# biochem_M_V2.net
KiCad netlist of a schematic drawn in EAGLE
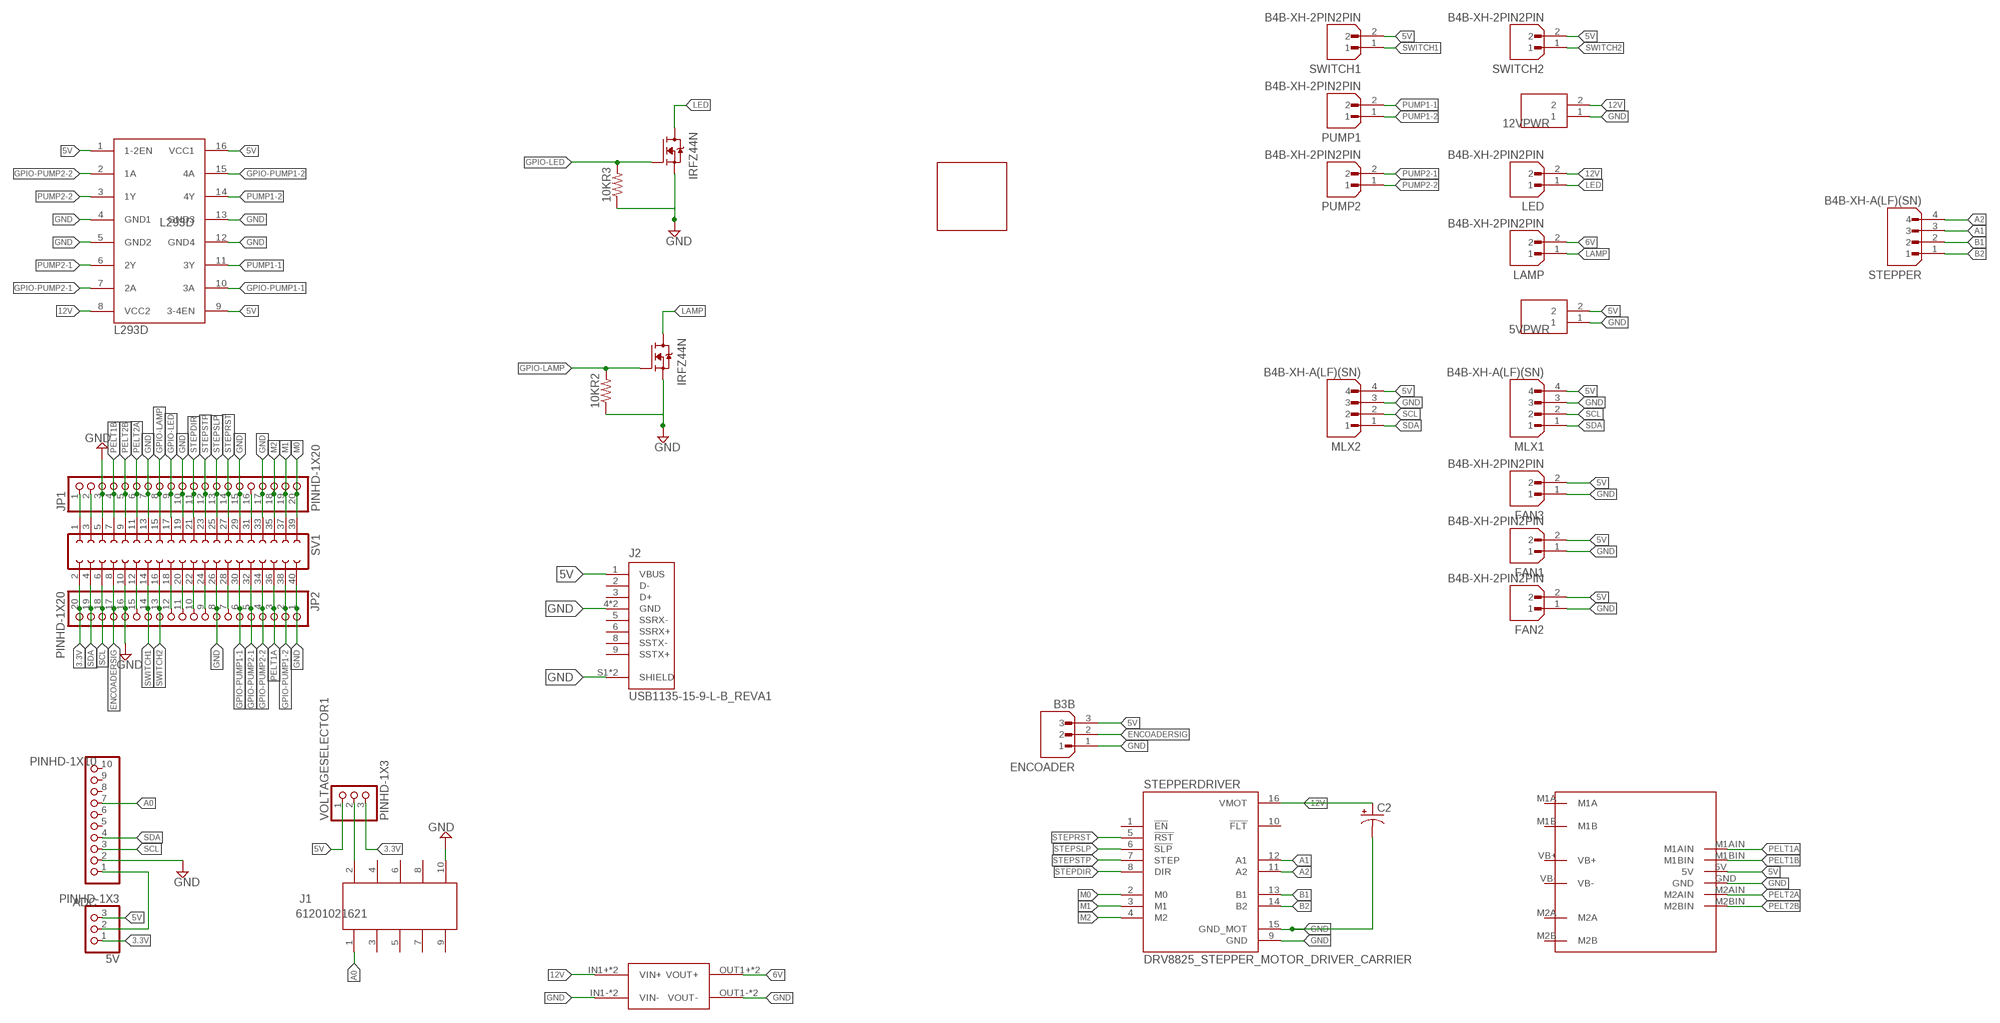
[diagram p0: schematic, sheet 1]

(export (version "E")
  (design (tool "Eeschema 10.0.6"))
  (components
    (comp (ref "5V")
      (value "PINHD-1X3")
      (footprint "eagle-import:1X03")
      (libsource (lib "eagle-import") (part "PINHD-1X3"))
    )
    (comp (ref "5VPWR")
      (value "TB010-508-02BE")
      (footprint "eagle-import:CUI_TB010-508-02BE")
      (fields (field (name "MF") "CUI Devices"))
      (libsource (lib "eagle-import") (part "TB010-508-02BE"))
    )
    (comp (ref "10KR2")
      (value "R-US_0204/7")
      (footprint "eagle-import:0204_7")
      (libsource (lib "eagle-import") (part "R-US_0204/7"))
    )
    (comp (ref "10KR3")
      (value "R-US_0204/7")
      (footprint "eagle-import:0204_7")
      (libsource (lib "eagle-import") (part "R-US_0204/7"))
    )
    (comp (ref "12VPWR")
      (value "TB010-508-02BE")
      (footprint "eagle-import:CUI_TB010-508-02BE")
      (fields (field (name "MF") "CUI Devices"))
      (libsource (lib "eagle-import") (part "TB010-508-02BE"))
    )
    (comp (ref "ADC")
      (value "PINHD-1X10")
      (footprint "eagle-import:1X10")
      (libsource (lib "eagle-import") (part "PINHD-1X10"))
    )
    (comp (ref "C2")
      (value "CPOL-USB45181A")
      (footprint "eagle-import:B45181A")
      (libsource (lib "eagle-import") (part "CPOL-USB45181A"))
    )
    (comp (ref "ENCOADER")
      (value "B3B")
      (footprint "eagle-import:B3B")
      (libsource (lib "eagle-import") (part "B3B"))
    )
    (comp (ref "FAN1")
      (value "B4B-XH-2PIN2PIN")
      (footprint "eagle-import:B4BXH2")
      (libsource (lib "eagle-import") (part "B4B-XH-2PIN2PIN"))
    )
    (comp (ref "FAN2")
      (value "B4B-XH-2PIN2PIN")
      (footprint "eagle-import:B4BXH2")
      (libsource (lib "eagle-import") (part "B4B-XH-2PIN2PIN"))
    )
    (comp (ref "FAN3")
      (value "B4B-XH-2PIN2PIN")
      (footprint "eagle-import:B4BXH2")
      (libsource (lib "eagle-import") (part "B4B-XH-2PIN2PIN"))
    )
    (comp (ref "J1")
      (value "61201021621")
      (footprint "eagle-import:61201021621")
      (fields (field (name "MF") "Wurth Elektronik"))
      (libsource (lib "eagle-import") (part "61201021621"))
    )
    (comp (ref "J2")
      (value "USB1135-15-9-L-B_REVA1")
      (footprint "eagle-import:GCT_USB1135-15-9-L-B_REVA1")
      (fields (field (name "MF") "Global Connector Technology") (field (name "MP") "USB1135-15-9-L-B"))
      (libsource (lib "eagle-import") (part "USB1135-15-9-L-B_REVA1"))
    )
    (comp (ref "JP1")
      (value "PINHD-1X20")
      (footprint "eagle-import:1X20")
      (libsource (lib "eagle-import") (part "PINHD-1X20"))
    )
    (comp (ref "JP2")
      (value "PINHD-1X20")
      (footprint "eagle-import:1X20")
      (libsource (lib "eagle-import") (part "PINHD-1X20"))
    )
    (comp (ref "L293D")
      (value "L293D")
      (footprint "eagle-import:DIL16")
      (libsource (lib "eagle-import") (part "L293D"))
    )
    (comp (ref "LAMP")
      (value "B4B-XH-2PIN2PIN")
      (footprint "eagle-import:B4BXH2")
      (libsource (lib "eagle-import") (part "B4B-XH-2PIN2PIN"))
    )
    (comp (ref "LED")
      (value "B4B-XH-2PIN2PIN")
      (footprint "eagle-import:B4BXH2")
      (libsource (lib "eagle-import") (part "B4B-XH-2PIN2PIN"))
    )
    (comp (ref "MLX1")
      (value "B4B-XH-A(LF)(SN)")
      (footprint "eagle-import:JST_B4B-XH-A(LF)(SN)")
      (fields (field (name "MF") "JST") (field (name "MP") "B4B-XH-A  (LF)(SN)"))
      (libsource (lib "eagle-import") (part "B4B-XH-A(LF)(SN)"))
    )
    (comp (ref "MLX2")
      (value "B4B-XH-A(LF)(SN)")
      (footprint "eagle-import:JST_B4B-XH-A(LF)(SN)")
      (fields (field (name "MF") "JST") (field (name "MP") "B4B-XH-A  (LF)(SN)"))
      (libsource (lib "eagle-import") (part "B4B-XH-A(LF)(SN)"))
    )
    (comp (ref "PUMP1")
      (value "B4B-XH-2PIN2PIN")
      (footprint "eagle-import:B4BXH2")
      (libsource (lib "eagle-import") (part "B4B-XH-2PIN2PIN"))
    )
    (comp (ref "PUMP2")
      (value "B4B-XH-2PIN2PIN")
      (footprint "eagle-import:B4BXH2")
      (libsource (lib "eagle-import") (part "B4B-XH-2PIN2PIN"))
    )
    (comp (ref "Q4-T")
      (value "IRFZ44N")
      (footprint "eagle-import:TO254P1016X419X2286-3")
      (fields (field (name "MF") "Infineon Technologies"))
      (libsource (lib "eagle-import") (part "IRFZ44N"))
    )
    (comp (ref "Q4-T4")
      (value "IRFZ44N")
      (footprint "eagle-import:TO254P1016X419X2286-3")
      (fields (field (name "MF") "Infineon Technologies"))
      (libsource (lib "eagle-import") (part "IRFZ44N"))
    )
    (comp (ref "STEPPER")
      (value "B4B-XH-A(LF)(SN)")
      (footprint "eagle-import:JST_B4B-XH-A(LF)(SN)")
      (fields (field (name "MF") "JST") (field (name "MP") "B4B-XH-A  (LF)(SN)"))
      (libsource (lib "eagle-import") (part "B4B-XH-A(LF)(SN)"))
    )
    (comp (ref "STEPPERDRIVER")
      (value "DRV8825_STEPPER_MOTOR_DRIVER_CARRIER")
      (footprint "eagle-import:IC_DRV8825_STEPPER_MOTOR_DRIVER_CARRIER")
      (fields (field (name "MF") "Pololu") (field (name "MP") "DRV8825 STEPPER MOTOR DRIVER CARRIER"))
      (libsource (lib "eagle-import") (part "DRV8825_STEPPER_MOTOR_DRIVER_CARRIER"))
    )
    (comp (ref "SV1")
      (value "FE20-2")
      (footprint "eagle-import:FE20-2")
      (libsource (lib "eagle-import") (part "FE20-2"))
    )
    (comp (ref "SWITCH1")
      (value "B4B-XH-2PIN2PIN")
      (footprint "eagle-import:B4BXH2")
      (libsource (lib "eagle-import") (part "B4B-XH-2PIN2PIN"))
    )
    (comp (ref "SWITCH2")
      (value "B4B-XH-2PIN2PIN")
      (footprint "eagle-import:B4BXH2")
      (libsource (lib "eagle-import") (part "B4B-XH-2PIN2PIN"))
    )
    (comp (ref "U$1")
      (value "MP1584")
      (footprint "eagle-import:DC-BRICK")
      (libsource (lib "eagle-import") (part "MP1584"))
    )
    (comp (ref "U$2")
      (value "MDD3A")
      (footprint "eagle-import:FOOTPRINT")
      (libsource (lib "eagle-import") (part "MDD3A"))
    )
    (comp (ref "U$3")
      (value "QRBIOS")
      (footprint "eagle-import:GITQRBIOSPECTRONICS")
      (libsource (lib "eagle-import") (part "QRBIOS"))
    )
    (comp (ref "VOLTAGESELECTOR1")
      (value "PINHD-1X3")
      (footprint "eagle-import:1X03")
      (libsource (lib "eagle-import") (part "PINHD-1X3"))
    )
  )
  (nets
    (net (code "1") (name "3.3V") (class "Default")
      (node (ref "5V") (pin "1") (pinfunction "1_1") (pintype "passive"))
      (node (ref "JP2") (pin "20") (pinfunction "20_20") (pintype "passive"))
      (node (ref "SV1") (pin "2") (pinfunction "2_2") (pintype "passive"))
      (node (ref "VOLTAGESELECTOR1") (pin "3") (pinfunction "3_3") (pintype "passive"))
    )
    (net (code "2") (name "5V") (class "Default")
      (node (ref "5V") (pin "3") (pinfunction "3_3") (pintype "passive"))
      (node (ref "5VPWR") (pin "2") (pinfunction "2_2") (pintype "passive"))
      (node (ref "ENCOADER") (pin "3") (pinfunction "3_3") (pintype "passive"))
      (node (ref "FAN1") (pin "2") (pinfunction "2_2") (pintype "passive"))
      (node (ref "FAN2") (pin "2") (pinfunction "2_2") (pintype "passive"))
      (node (ref "FAN3") (pin "2") (pinfunction "2_2") (pintype "passive"))
      (node (ref "J2") (pin "1") (pinfunction "VBUS_1") (pintype "power_in"))
      (node (ref "L293D") (pin "1") (pinfunction "1-2EN_1") (pintype "input"))
      (node (ref "L293D") (pin "16") (pinfunction "VCC1_16") (pintype "power_in"))
      (node (ref "L293D") (pin "9") (pinfunction "3-4EN_9") (pintype "input"))
      (node (ref "MLX1") (pin "4") (pinfunction "4_4") (pintype "passive"))
      (node (ref "MLX2") (pin "4") (pinfunction "4_4") (pintype "passive"))
      (node (ref "SWITCH1") (pin "2") (pinfunction "2_2") (pintype "passive"))
      (node (ref "SWITCH2") (pin "2") (pinfunction "2_2") (pintype "passive"))
      (node (ref "U$2") (pin "5V") (pinfunction "5V_5V") (pintype "bidirectional"))
      (node (ref "VOLTAGESELECTOR1") (pin "1") (pinfunction "1_1") (pintype "passive"))
    )
    (net (code "3") (name "6V") (class "Default")
      (node (ref "LAMP") (pin "2") (pinfunction "2_2") (pintype "passive"))
      (node (ref "U$1") (pin "OUT1+") (pinfunction "VOUT+_OUT1+") (pintype "output"))
      (node (ref "U$1") (pin "OUT2+") (pinfunction "VOUT+_OUT2+") (pintype "output"))
    )
    (net (code "4") (name "12V") (class "Default")
      (node (ref "12VPWR") (pin "2") (pinfunction "2_2") (pintype "passive"))
      (node (ref "C2") (pin "+") (pinfunction "+_+") (pintype "passive"))
      (node (ref "L293D") (pin "8") (pinfunction "VCC2_8") (pintype "power_in"))
      (node (ref "LED") (pin "2") (pinfunction "2_2") (pintype "passive"))
      (node (ref "STEPPERDRIVER") (pin "16") (pinfunction "VMOT_16") (pintype "power_in"))
      (node (ref "U$1") (pin "IN1+") (pinfunction "VIN+_IN1+") (pintype "input"))
      (node (ref "U$1") (pin "IN2+") (pinfunction "VIN+_IN2+") (pintype "input"))
    )
    (net (code "5") (name "A0") (class "Default")
      (node (ref "ADC") (pin "7") (pinfunction "7_7") (pintype "passive"))
      (node (ref "J1") (pin "1") (pinfunction "1_1") (pintype "passive"))
    )
    (net (code "6") (name "A1") (class "Default")
      (node (ref "STEPPER") (pin "3") (pinfunction "3_3") (pintype "passive"))
      (node (ref "STEPPERDRIVER") (pin "12") (pinfunction "A1_12") (pintype "output"))
    )
    (net (code "7") (name "A2") (class "Default")
      (node (ref "STEPPER") (pin "4") (pinfunction "4_4") (pintype "passive"))
      (node (ref "STEPPERDRIVER") (pin "11") (pinfunction "A2_11") (pintype "output"))
    )
    (net (code "8") (name "B1") (class "Default")
      (node (ref "STEPPER") (pin "2") (pinfunction "2_2") (pintype "passive"))
      (node (ref "STEPPERDRIVER") (pin "13") (pinfunction "B1_13") (pintype "output"))
    )
    (net (code "9") (name "B2") (class "Default")
      (node (ref "STEPPER") (pin "1") (pinfunction "1_1") (pintype "passive"))
      (node (ref "STEPPERDRIVER") (pin "14") (pinfunction "B2_14") (pintype "output"))
    )
    (net (code "10") (name "ENCOADERSIG") (class "Default")
      (node (ref "ENCOADER") (pin "2") (pinfunction "2_2") (pintype "passive"))
      (node (ref "JP2") (pin "17") (pinfunction "17_17") (pintype "passive"))
      (node (ref "SV1") (pin "8") (pinfunction "8_8") (pintype "passive"))
    )
    (net (code "11") (name "GND") (class "Default")
      (node (ref "10KR2") (pin "1") (pinfunction "1_1") (pintype "passive"))
      (node (ref "10KR3") (pin "1") (pinfunction "1_1") (pintype "passive"))
      (node (ref "12VPWR") (pin "1") (pinfunction "1_1") (pintype "passive"))
      (node (ref "5VPWR") (pin "1") (pinfunction "1_1") (pintype "passive"))
      (node (ref "ADC") (pin "2") (pinfunction "2_2") (pintype "passive"))
      (node (ref "C2") (pin "-") (pinfunction "-_-") (pintype "passive"))
      (node (ref "ENCOADER") (pin "1") (pinfunction "1_1") (pintype "passive"))
      (node (ref "FAN1") (pin "1") (pinfunction "1_1") (pintype "passive"))
      (node (ref "FAN2") (pin "1") (pinfunction "1_1") (pintype "passive"))
      (node (ref "FAN3") (pin "1") (pinfunction "1_1") (pintype "passive"))
      (node (ref "J1") (pin "10") (pinfunction "10_10") (pintype "passive"))
      (node (ref "J2") (pin "4") (pinfunction "GND_4") (pintype "power_in"))
      (node (ref "J2") (pin "7") (pinfunction "GND_7") (pintype "power_in"))
      (node (ref "J2") (pin "S1") (pinfunction "SHIELD_S1") (pintype "passive"))
      (node (ref "J2") (pin "S2") (pinfunction "SHIELD_S2") (pintype "passive"))
      (node (ref "JP1") (pin "10") (pinfunction "10_10") (pintype "passive"))
      (node (ref "JP1") (pin "15") (pinfunction "15_15") (pintype "passive"))
      (node (ref "JP1") (pin "17") (pinfunction "17_17") (pintype "passive"))
      (node (ref "JP1") (pin "3") (pinfunction "3_3") (pintype "passive"))
      (node (ref "JP1") (pin "7") (pinfunction "7_7") (pintype "passive"))
      (node (ref "JP2") (pin "1") (pinfunction "1_1") (pintype "passive"))
      (node (ref "JP2") (pin "16") (pinfunction "16_16") (pintype "passive"))
      (node (ref "JP2") (pin "8") (pinfunction "8_8") (pintype "passive"))
      (node (ref "L293D") (pin "12") (pinfunction "GND4_12") (pintype "power_in"))
      (node (ref "L293D") (pin "13") (pinfunction "GND3_13") (pintype "power_in"))
      (node (ref "L293D") (pin "4") (pinfunction "GND1_4") (pintype "power_in"))
      (node (ref "L293D") (pin "5") (pinfunction "GND2_5") (pintype "power_in"))
      (node (ref "MLX1") (pin "3") (pinfunction "3_3") (pintype "passive"))
      (node (ref "MLX2") (pin "3") (pinfunction "3_3") (pintype "passive"))
      (node (ref "Q4-T") (pin "3") (pinfunction "S_3") (pintype "passive"))
      (node (ref "Q4-T4") (pin "3") (pinfunction "S_3") (pintype "passive"))
      (node (ref "STEPPERDRIVER") (pin "15") (pinfunction "GND_MOT_15") (pintype "power_in"))
      (node (ref "STEPPERDRIVER") (pin "9") (pinfunction "GND_9") (pintype "power_in"))
      (node (ref "SV1") (pin "10") (pinfunction "10_10") (pintype "passive"))
      (node (ref "SV1") (pin "13") (pinfunction "13_13") (pintype "passive"))
      (node (ref "SV1") (pin "19") (pinfunction "19_19") (pintype "passive"))
      (node (ref "SV1") (pin "26") (pinfunction "26_26") (pintype "passive"))
      (node (ref "SV1") (pin "29") (pinfunction "29_29") (pintype "passive"))
      (node (ref "SV1") (pin "33") (pinfunction "33_33") (pintype "passive"))
      (node (ref "SV1") (pin "40") (pinfunction "40_40") (pintype "passive"))
      (node (ref "SV1") (pin "5") (pinfunction "5_5") (pintype "passive"))
      (node (ref "U$1") (pin "IN1-") (pinfunction "VIN-_IN1-") (pintype "input"))
      (node (ref "U$1") (pin "IN2-") (pinfunction "VIN-_IN2-") (pintype "input"))
      (node (ref "U$1") (pin "OUT1-") (pinfunction "VOUT-_OUT1-") (pintype "output"))
      (node (ref "U$1") (pin "OUT2-") (pinfunction "VOUT-_OUT2-") (pintype "output"))
      (node (ref "U$2") (pin "GND") (pinfunction "GND_GND") (pintype "bidirectional"))
    )
    (net (code "12") (name "GPIO-LAMP") (class "Default")
      (node (ref "10KR2") (pin "2") (pinfunction "2_2") (pintype "passive"))
      (node (ref "JP1") (pin "8") (pinfunction "8_8") (pintype "passive"))
      (node (ref "Q4-T") (pin "1") (pinfunction "G_1") (pintype "passive"))
      (node (ref "SV1") (pin "15") (pinfunction "15_15") (pintype "passive"))
    )
    (net (code "13") (name "GPIO-LED") (class "Default")
      (node (ref "10KR3") (pin "2") (pinfunction "2_2") (pintype "passive"))
      (node (ref "JP1") (pin "9") (pinfunction "9_9") (pintype "passive"))
      (node (ref "Q4-T4") (pin "1") (pinfunction "G_1") (pintype "passive"))
      (node (ref "SV1") (pin "17") (pinfunction "17_17") (pintype "passive"))
    )
    (net (code "14") (name "GPIO-PUMP1-1") (class "Default")
      (node (ref "JP2") (pin "6") (pinfunction "6_6") (pintype "passive"))
      (node (ref "L293D") (pin "10") (pinfunction "3A_10") (pintype "input"))
      (node (ref "SV1") (pin "30") (pinfunction "30_30") (pintype "passive"))
    )
    (net (code "15") (name "GPIO-PUMP1-2") (class "Default")
      (node (ref "JP2") (pin "2") (pinfunction "2_2") (pintype "passive"))
      (node (ref "L293D") (pin "15") (pinfunction "4A_15") (pintype "input"))
      (node (ref "SV1") (pin "38") (pinfunction "38_38") (pintype "passive"))
    )
    (net (code "16") (name "GPIO-PUMP2-1") (class "Default")
      (node (ref "JP2") (pin "5") (pinfunction "5_5") (pintype "passive"))
      (node (ref "L293D") (pin "7") (pinfunction "2A_7") (pintype "input"))
      (node (ref "SV1") (pin "32") (pinfunction "32_32") (pintype "passive"))
    )
    (net (code "17") (name "GPIO-PUMP2-2") (class "Default")
      (node (ref "JP2") (pin "4") (pinfunction "4_4") (pintype "passive"))
      (node (ref "L293D") (pin "2") (pinfunction "1A_2") (pintype "input"))
      (node (ref "SV1") (pin "34") (pinfunction "34_34") (pintype "passive"))
    )
    (net (code "18") (name "LAMP") (class "Default")
      (node (ref "LAMP") (pin "1") (pinfunction "1_1") (pintype "passive"))
      (node (ref "Q4-T") (pin "2") (pinfunction "D_2") (pintype "passive"))
    )
    (net (code "19") (name "LED") (class "Default")
      (node (ref "LED") (pin "1") (pinfunction "1_1") (pintype "passive"))
      (node (ref "Q4-T4") (pin "2") (pinfunction "D_2") (pintype "passive"))
    )
    (net (code "20") (name "M0") (class "Default")
      (node (ref "JP1") (pin "20") (pinfunction "20_20") (pintype "passive"))
      (node (ref "STEPPERDRIVER") (pin "2") (pinfunction "M0_2") (pintype "input"))
      (node (ref "SV1") (pin "39") (pinfunction "39_39") (pintype "passive"))
    )
    (net (code "21") (name "M1") (class "Default")
      (node (ref "JP1") (pin "19") (pinfunction "19_19") (pintype "passive"))
      (node (ref "STEPPERDRIVER") (pin "3") (pinfunction "M1_3") (pintype "input"))
      (node (ref "SV1") (pin "37") (pinfunction "37_37") (pintype "passive"))
    )
    (net (code "22") (name "M2") (class "Default")
      (node (ref "JP1") (pin "18") (pinfunction "18_18") (pintype "passive"))
      (node (ref "STEPPERDRIVER") (pin "4") (pinfunction "M2_4") (pintype "input"))
      (node (ref "SV1") (pin "35") (pinfunction "35_35") (pintype "passive"))
    )
    (net (code "23") (name "Net-(5V-Pad2)") (class "Default")
      (node (ref "5V") (pin "2") (pinfunction "2_2") (pintype "passive"))
      (node (ref "ADC") (pin "1") (pinfunction "1_1") (pintype "passive"))
    )
    (net (code "24") (name "Net-(J1-Pad2)") (class "Default")
      (node (ref "J1") (pin "2") (pinfunction "2_2") (pintype "passive"))
      (node (ref "VOLTAGESELECTOR1") (pin "2") (pinfunction "2_2") (pintype "passive"))
    )
    (net (code "25") (name "Net-(JP1-Pad1)") (class "Default")
      (node (ref "JP1") (pin "1") (pinfunction "1_1") (pintype "passive"))
      (node (ref "SV1") (pin "1") (pinfunction "1_1") (pintype "passive"))
    )
    (net (code "26") (name "Net-(JP1-Pad2)") (class "Default")
      (node (ref "JP1") (pin "2") (pinfunction "2_2") (pintype "passive"))
      (node (ref "SV1") (pin "3") (pinfunction "3_3") (pintype "passive"))
    )
    (net (code "27") (name "Net-(JP1-Pad16)") (class "Default")
      (node (ref "JP1") (pin "16") (pinfunction "16_16") (pintype "passive"))
      (node (ref "SV1") (pin "31") (pinfunction "31_31") (pintype "passive"))
    )
    (net (code "28") (name "Net-(JP2-Pad7)") (class "Default")
      (node (ref "JP2") (pin "7") (pinfunction "7_7") (pintype "passive"))
      (node (ref "SV1") (pin "28") (pinfunction "28_28") (pintype "passive"))
    )
    (net (code "29") (name "Net-(JP2-Pad9)") (class "Default")
      (node (ref "JP2") (pin "9") (pinfunction "9_9") (pintype "passive"))
      (node (ref "SV1") (pin "24") (pinfunction "24_24") (pintype "passive"))
    )
    (net (code "30") (name "Net-(JP2-Pad10)") (class "Default")
      (node (ref "JP2") (pin "10") (pinfunction "10_10") (pintype "passive"))
      (node (ref "SV1") (pin "22") (pinfunction "22_22") (pintype "passive"))
    )
    (net (code "31") (name "Net-(JP2-Pad11)") (class "Default")
      (node (ref "JP2") (pin "11") (pinfunction "11_11") (pintype "passive"))
      (node (ref "SV1") (pin "20") (pinfunction "20_20") (pintype "passive"))
    )
    (net (code "32") (name "Net-(JP2-Pad12)") (class "Default")
      (node (ref "JP2") (pin "12") (pinfunction "12_12") (pintype "passive"))
      (node (ref "SV1") (pin "18") (pinfunction "18_18") (pintype "passive"))
    )
    (net (code "33") (name "Net-(JP2-Pad15)") (class "Default")
      (node (ref "JP2") (pin "15") (pinfunction "15_15") (pintype "passive"))
      (node (ref "SV1") (pin "12") (pinfunction "12_12") (pintype "passive"))
    )
    (net (code "34") (name "PELT1A") (class "Default")
      (node (ref "JP2") (pin "3") (pinfunction "3_3") (pintype "passive"))
      (node (ref "SV1") (pin "36") (pinfunction "36_36") (pintype "passive"))
      (node (ref "U$2") (pin "M1AIN") (pinfunction "M1AIN_M1AIN") (pintype "bidirectional"))
    )
    (net (code "35") (name "PELT1B") (class "Default")
      (node (ref "JP1") (pin "4") (pinfunction "4_4") (pintype "passive"))
      (node (ref "SV1") (pin "7") (pinfunction "7_7") (pintype "passive"))
      (node (ref "U$2") (pin "M1BIN") (pinfunction "M1BIN_M1BIN") (pintype "bidirectional"))
    )
    (net (code "36") (name "PELT2A") (class "Default")
      (node (ref "JP1") (pin "6") (pinfunction "6_6") (pintype "passive"))
      (node (ref "SV1") (pin "11") (pinfunction "11_11") (pintype "passive"))
      (node (ref "U$2") (pin "M2AIN") (pinfunction "M2AIN_M2AIN") (pintype "bidirectional"))
    )
    (net (code "37") (name "PELT2B") (class "Default")
      (node (ref "JP1") (pin "5") (pinfunction "5_5") (pintype "passive"))
      (node (ref "SV1") (pin "9") (pinfunction "9_9") (pintype "passive"))
      (node (ref "U$2") (pin "M2BIN") (pinfunction "M2BIN_M2BIN") (pintype "bidirectional"))
    )
    (net (code "38") (name "PUMP1-1") (class "Default")
      (node (ref "L293D") (pin "11") (pinfunction "3Y_11") (pintype "output"))
      (node (ref "PUMP1") (pin "2") (pinfunction "2_2") (pintype "passive"))
    )
    (net (code "39") (name "PUMP1-2") (class "Default")
      (node (ref "L293D") (pin "14") (pinfunction "4Y_14") (pintype "output"))
      (node (ref "PUMP1") (pin "1") (pinfunction "1_1") (pintype "passive"))
    )
    (net (code "40") (name "PUMP2-1") (class "Default")
      (node (ref "L293D") (pin "6") (pinfunction "2Y_6") (pintype "output"))
      (node (ref "PUMP2") (pin "2") (pinfunction "2_2") (pintype "passive"))
    )
    (net (code "41") (name "PUMP2-2") (class "Default")
      (node (ref "L293D") (pin "3") (pinfunction "1Y_3") (pintype "output"))
      (node (ref "PUMP2") (pin "1") (pinfunction "1_1") (pintype "passive"))
    )
    (net (code "42") (name "SCL") (class "Default")
      (node (ref "ADC") (pin "3") (pinfunction "3_3") (pintype "passive"))
      (node (ref "JP2") (pin "18") (pinfunction "18_18") (pintype "passive"))
      (node (ref "MLX1") (pin "2") (pinfunction "2_2") (pintype "passive"))
      (node (ref "MLX2") (pin "2") (pinfunction "2_2") (pintype "passive"))
      (node (ref "SV1") (pin "6") (pinfunction "6_6") (pintype "passive"))
    )
    (net (code "43") (name "SDA") (class "Default")
      (node (ref "ADC") (pin "4") (pinfunction "4_4") (pintype "passive"))
      (node (ref "JP2") (pin "19") (pinfunction "19_19") (pintype "passive"))
      (node (ref "MLX1") (pin "1") (pinfunction "1_1") (pintype "passive"))
      (node (ref "MLX2") (pin "1") (pinfunction "1_1") (pintype "passive"))
      (node (ref "SV1") (pin "4") (pinfunction "4_4") (pintype "passive"))
    )
    (net (code "44") (name "STEPDIR") (class "Default")
      (node (ref "JP1") (pin "11") (pinfunction "11_11") (pintype "passive"))
      (node (ref "STEPPERDRIVER") (pin "8") (pinfunction "DIR_8") (pintype "input"))
      (node (ref "SV1") (pin "21") (pinfunction "21_21") (pintype "passive"))
    )
    (net (code "45") (name "STEPRST") (class "Default")
      (node (ref "JP1") (pin "14") (pinfunction "14_14") (pintype "passive"))
      (node (ref "STEPPERDRIVER") (pin "5") (pinfunction "~{RST}_5") (pintype "input"))
      (node (ref "SV1") (pin "27") (pinfunction "27_27") (pintype "passive"))
    )
    (net (code "46") (name "STEPSLP") (class "Default")
      (node (ref "JP1") (pin "13") (pinfunction "13_13") (pintype "passive"))
      (node (ref "STEPPERDRIVER") (pin "6") (pinfunction "~{SLP}_6") (pintype "input"))
      (node (ref "SV1") (pin "25") (pinfunction "25_25") (pintype "passive"))
    )
    (net (code "47") (name "STEPSTP") (class "Default")
      (node (ref "JP1") (pin "12") (pinfunction "12_12") (pintype "passive"))
      (node (ref "STEPPERDRIVER") (pin "7") (pinfunction "STEP_7") (pintype "input"))
      (node (ref "SV1") (pin "23") (pinfunction "23_23") (pintype "passive"))
    )
    (net (code "48") (name "SWITCH1") (class "Default")
      (node (ref "JP2") (pin "14") (pinfunction "14_14") (pintype "passive"))
      (node (ref "SV1") (pin "14") (pinfunction "14_14") (pintype "passive"))
      (node (ref "SWITCH1") (pin "1") (pinfunction "1_1") (pintype "passive"))
    )
    (net (code "49") (name "SWITCH2") (class "Default")
      (node (ref "JP2") (pin "13") (pinfunction "13_13") (pintype "passive"))
      (node (ref "SV1") (pin "16") (pinfunction "16_16") (pintype "passive"))
      (node (ref "SWITCH2") (pin "1") (pinfunction "1_1") (pintype "passive"))
    )
    (net (code "50") (name "unconnected-(ADC-Pad5)") (class "Default")
      (node (ref "ADC") (pin "5") (pinfunction "5_5") (pintype "passive"))
    )
    (net (code "51") (name "unconnected-(ADC-Pad6)") (class "Default")
      (node (ref "ADC") (pin "6") (pinfunction "6_6") (pintype "passive"))
    )
    (net (code "52") (name "unconnected-(ADC-Pad8)") (class "Default")
      (node (ref "ADC") (pin "8") (pinfunction "8_8") (pintype "passive"))
    )
    (net (code "53") (name "unconnected-(ADC-Pad9)") (class "Default")
      (node (ref "ADC") (pin "9") (pinfunction "9_9") (pintype "passive"))
    )
    (net (code "54") (name "unconnected-(ADC-Pad10)") (class "Default")
      (node (ref "ADC") (pin "10") (pinfunction "10_10") (pintype "passive"))
    )
    (net (code "55") (name "unconnected-(J1-Pad3)") (class "Default")
      (node (ref "J1") (pin "3") (pinfunction "3_3") (pintype "passive"))
    )
    (net (code "56") (name "unconnected-(J1-Pad4)") (class "Default")
      (node (ref "J1") (pin "4") (pinfunction "4_4") (pintype "passive"))
    )
    (net (code "57") (name "unconnected-(J1-Pad5)") (class "Default")
      (node (ref "J1") (pin "5") (pinfunction "5_5") (pintype "passive"))
    )
    (net (code "58") (name "unconnected-(J1-Pad6)") (class "Default")
      (node (ref "J1") (pin "6") (pinfunction "6_6") (pintype "passive"))
    )
    (net (code "59") (name "unconnected-(J1-Pad7)") (class "Default")
      (node (ref "J1") (pin "7") (pinfunction "7_7") (pintype "passive"))
    )
    (net (code "60") (name "unconnected-(J1-Pad8)") (class "Default")
      (node (ref "J1") (pin "8") (pinfunction "8_8") (pintype "passive"))
    )
    (net (code "61") (name "unconnected-(J1-Pad9)") (class "Default")
      (node (ref "J1") (pin "9") (pinfunction "9_9") (pintype "passive"))
    )
    (net (code "62") (name "unconnected-(J2-D+-Pad3)") (class "Default")
      (node (ref "J2") (pin "3") (pinfunction "D+_3") (pintype "bidirectional"))
    )
    (net (code "63") (name "unconnected-(J2-D--Pad2)") (class "Default")
      (node (ref "J2") (pin "2") (pinfunction "D-_2") (pintype "bidirectional"))
    )
    (net (code "64") (name "unconnected-(J2-SSRX+-Pad6)") (class "Default")
      (node (ref "J2") (pin "6") (pinfunction "SSRX+_6") (pintype "bidirectional"))
    )
    (net (code "65") (name "unconnected-(J2-SSRX--Pad5)") (class "Default")
      (node (ref "J2") (pin "5") (pinfunction "SSRX-_5") (pintype "bidirectional"))
    )
    (net (code "66") (name "unconnected-(J2-SSTX+-Pad9)") (class "Default")
      (node (ref "J2") (pin "9") (pinfunction "SSTX+_9") (pintype "bidirectional"))
    )
    (net (code "67") (name "unconnected-(J2-SSTX--Pad8)") (class "Default")
      (node (ref "J2") (pin "8") (pinfunction "SSTX-_8") (pintype "bidirectional"))
    )
    (net (code "68") (name "unconnected-(STEPPERDRIVER-~{EN}-Pad1)") (class "Default")
      (node (ref "STEPPERDRIVER") (pin "1") (pinfunction "~{EN}_1") (pintype "input"))
    )
    (net (code "69") (name "unconnected-(STEPPERDRIVER-~{FLT}-Pad10)") (class "Default")
      (node (ref "STEPPERDRIVER") (pin "10") (pinfunction "~{FLT}_10") (pintype "output"))
    )
    (net (code "70") (name "unconnected-(U$2-PadM1A)") (class "Default")
      (node (ref "U$2") (pin "M1A") (pinfunction "M1A_M1A") (pintype "bidirectional"))
    )
    (net (code "71") (name "unconnected-(U$2-PadM1B)") (class "Default")
      (node (ref "U$2") (pin "M1B") (pinfunction "M1B_M1B") (pintype "bidirectional"))
    )
    (net (code "72") (name "unconnected-(U$2-PadM2A)") (class "Default")
      (node (ref "U$2") (pin "M2A") (pinfunction "M2A_M2A") (pintype "bidirectional"))
    )
    (net (code "73") (name "unconnected-(U$2-PadM2B)") (class "Default")
      (node (ref "U$2") (pin "M2B") (pinfunction "M2B_M2B") (pintype "bidirectional"))
    )
    (net (code "74") (name "unconnected-(U$2-PadVB+)") (class "Default")
      (node (ref "U$2") (pin "VB+") (pinfunction "VB+_VB+") (pintype "bidirectional"))
    )
    (net (code "75") (name "unconnected-(U$2-PadVB-)") (class "Default")
      (node (ref "U$2") (pin "VB-") (pinfunction "VB-_VB-") (pintype "bidirectional"))
    )
  )
)
